# 13-AM64x-02.net
KiCad netlist of a schematic drawn in Altium Designer
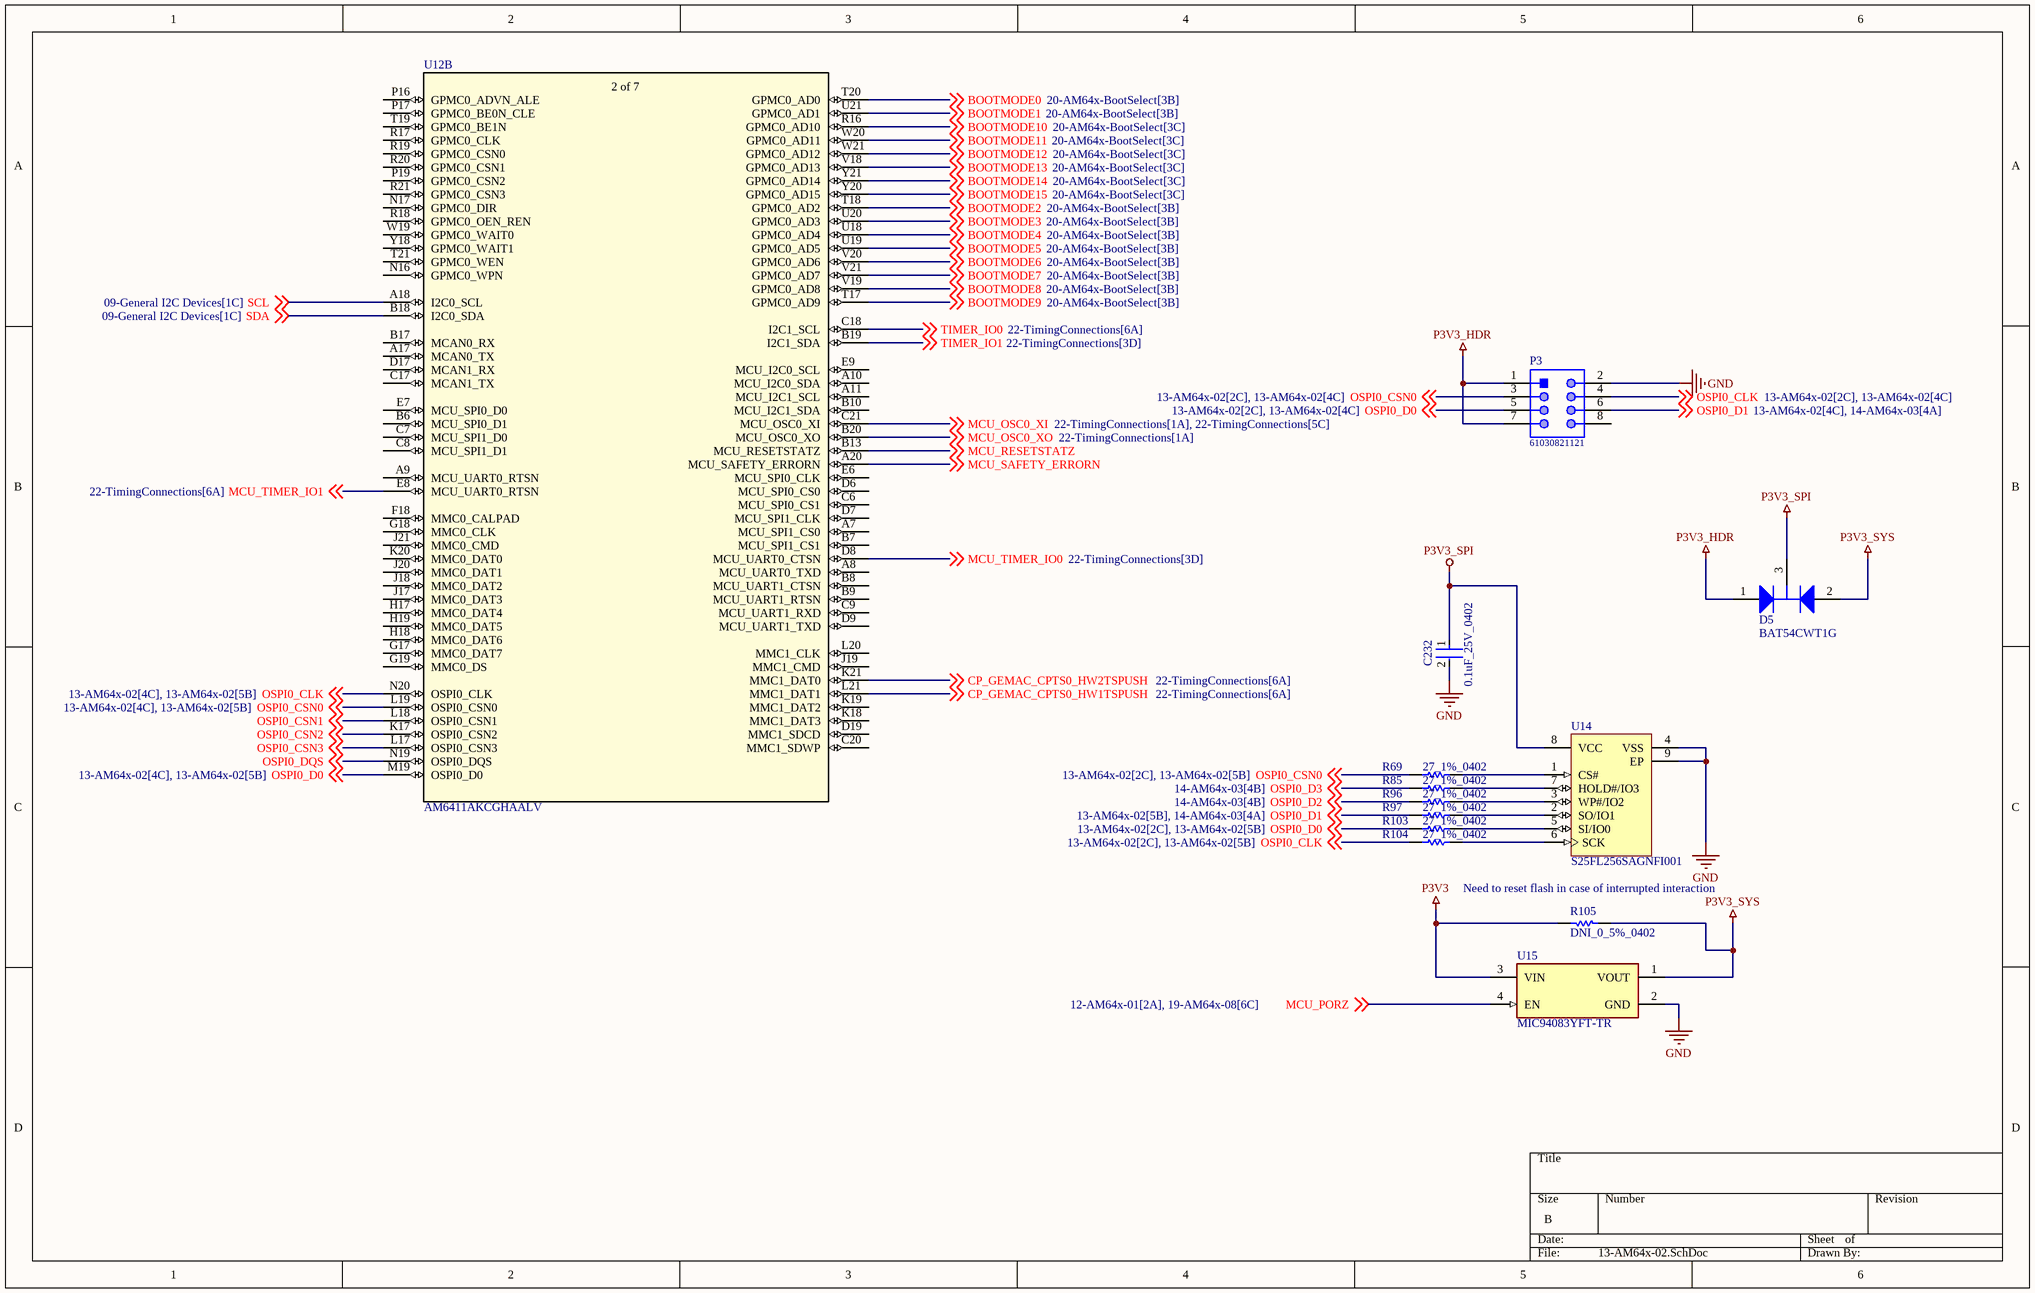
[diagram p0: 13-AM64x-02.SchDoc]

(export (version "E")
  (design (tool "Eeschema 10.0.6"))
  (components
    (comp (ref "C232")
      (value "0.1uF_25V_0402")
      (footprint "FP-0402-L_1_0_1-W_0_5_0_1-IPC_C")
      (description "General Purpose Ceramic Capacitor, 0402, 100nF, 10%, X7R, 15%, 25V")
      (fields (field (name "VOLTAGE") "25V") (field (name "TOLERANCE") "10%"))
      (libsource (lib "Altium Content Vault") (part "b4654b650e69147ec39a6b967a45e02"))
    )
    (comp (ref "D5")
      (value "BAT54CWT1G")
      (footprint "ONSC-SOT-323-3-419-04_V")
      (description "Dual Series Cathode Schottky Barrier Diodes, 3-Pin SOT-323, Pb-Free, Tape and Reel")
      (fields (field (name "MANUFACTURER") "On Semiconductor"))
      (libsource (lib "Altium Content Vault") (part "ONSC-D-A1A2K3-3"))
    )
    (comp (ref "P3")
      (value "61030821121")
      (footprint "61030821121")
      (description "SMT Vertical Pin Header WR-PHD, Pitch 2.54 mm, Dual Row, 8 pins")
      (fields (field (name "MANUFACTURER") "Wurth Elektronik") (field (name "PUBLISHER") "WurthElektronik"))
      (libsource (lib "Altium Content Vault") (part "WE-CN-2P-M-R8"))
    )
    (comp (ref "R69")
      (value "27_1%_0402")
      (footprint "RESC1005X40X25NL05T05")
      (fields (field (name "PART NUMBER") "CRCW040227R0FKED") (field (name "MANUFACTURER") "Vishay Dale"))
      (libsource (lib "Altium Content Vault") (part "RES"))
    )
    (comp (ref "R85")
      (value "27_1%_0402")
      (footprint "RESC1005X40X25NL05T05")
      (fields (field (name "PART NUMBER") "CRCW040227R0FKED") (field (name "MANUFACTURER") "Vishay Dale"))
      (libsource (lib "Altium Content Vault") (part "RES"))
    )
    (comp (ref "R96")
      (value "27_1%_0402")
      (footprint "RESC1005X40X25NL05T05")
      (fields (field (name "PART NUMBER") "CRCW040227R0FKED") (field (name "MANUFACTURER") "Vishay Dale"))
      (libsource (lib "Altium Content Vault") (part "RES"))
    )
    (comp (ref "R97")
      (value "27_1%_0402")
      (footprint "RESC1005X40X25NL05T05")
      (fields (field (name "PART NUMBER") "CRCW040227R0FKED") (field (name "MANUFACTURER") "Vishay Dale"))
      (libsource (lib "Altium Content Vault") (part "RES"))
    )
    (comp (ref "R103")
      (value "27_1%_0402")
      (footprint "RESC1005X40X25NL05T05")
      (fields (field (name "PART NUMBER") "CRCW040227R0FKED") (field (name "MANUFACTURER") "Vishay Dale"))
      (libsource (lib "Altium Content Vault") (part "RES"))
    )
    (comp (ref "R104")
      (value "27_1%_0402")
      (footprint "RESC1005X40X25NL05T05")
      (fields (field (name "PART NUMBER") "CRCW040227R0FKED") (field (name "MANUFACTURER") "Vishay Dale"))
      (libsource (lib "Altium Content Vault") (part "RES"))
    )
    (comp (ref "R105")
      (value "DNI_0_5%_0402")
      (footprint "RESC1005X40X25LL10T10")
      (fields (field (name "MANUFACTURER") "KOA Speer") (field (name "PART NUMBER") "RK73Z1ETTP"))
      (libsource (lib "Altium Content Vault") (part "RES"))
    )
    (comp (ref "U12")
      (value "AM6411AKCGHAALV")
      (footprint "FCBGA441_ALV_TEX")
      (description "No Description Available")
      (libsource (lib "AM6411AKCGHAALV") (part "AM6411AKCGHAALV"))
    )
    (comp (ref "U14")
      (value "S25FL256SAGNFI001")
      (footprint "CYP-WSON-8_L")
      (description "SPI Flash Memory, 2.7 to 3.6 V, -40 to 85 degC, 8-Pin WSON, RoHS, Tube")
      (fields (field (name "MANUFACTURER") "CypressSemiconductorCorp"))
      (libsource (lib "Altium Content Vault") (part "CYP-S25FL256S-WSON-8"))
    )
    (comp (ref "U15")
      (value "MIC94083YFT-TR")
      (footprint "FP-FTDFN085085-4LD-PL-1-MFG")
      (description "IC PWR SWITCH P-CHAN 1:1 4TMLF")
      (libsource (lib "Altium Content Vault") (part "f982b0e4379ad1be1c154354d61e319"))
    )
  )
  (nets
    (net (code "1") (name "BOOTMODE0") (class "Default")
      (node (ref "U12") (pin "T20") (pinfunction "GPMC0_AD0_T20") (pintype "bidirectional"))
    )
    (net (code "2") (name "BOOTMODE1") (class "Default")
      (node (ref "U12") (pin "U21") (pinfunction "GPMC0_AD1_U21") (pintype "bidirectional"))
    )
    (net (code "3") (name "BOOTMODE2") (class "Default")
      (node (ref "U12") (pin "T18") (pinfunction "GPMC0_AD2_T18") (pintype "bidirectional"))
    )
    (net (code "4") (name "BOOTMODE3") (class "Default")
      (node (ref "U12") (pin "U20") (pinfunction "GPMC0_AD3_U20") (pintype "bidirectional"))
    )
    (net (code "5") (name "BOOTMODE4") (class "Default")
      (node (ref "U12") (pin "U18") (pinfunction "GPMC0_AD4_U18") (pintype "bidirectional"))
    )
    (net (code "6") (name "BOOTMODE5") (class "Default")
      (node (ref "U12") (pin "U19") (pinfunction "GPMC0_AD5_U19") (pintype "bidirectional"))
    )
    (net (code "7") (name "BOOTMODE6") (class "Default")
      (node (ref "U12") (pin "V20") (pinfunction "GPMC0_AD6_V20") (pintype "bidirectional"))
    )
    (net (code "8") (name "BOOTMODE7") (class "Default")
      (node (ref "U12") (pin "V21") (pinfunction "GPMC0_AD7_V21") (pintype "bidirectional"))
    )
    (net (code "9") (name "BOOTMODE8") (class "Default")
      (node (ref "U12") (pin "V19") (pinfunction "GPMC0_AD8_V19") (pintype "bidirectional"))
    )
    (net (code "10") (name "BOOTMODE9") (class "Default")
      (node (ref "U12") (pin "T17") (pinfunction "GPMC0_AD9_T17") (pintype "bidirectional"))
    )
    (net (code "11") (name "BOOTMODE10") (class "Default")
      (node (ref "U12") (pin "R16") (pinfunction "GPMC0_AD10_R16") (pintype "bidirectional"))
    )
    (net (code "12") (name "BOOTMODE11") (class "Default")
      (node (ref "U12") (pin "W20") (pinfunction "GPMC0_AD11_W20") (pintype "bidirectional"))
    )
    (net (code "13") (name "BOOTMODE12") (class "Default")
      (node (ref "U12") (pin "W21") (pinfunction "GPMC0_AD12_W21") (pintype "bidirectional"))
    )
    (net (code "14") (name "BOOTMODE13") (class "Default")
      (node (ref "U12") (pin "V18") (pinfunction "GPMC0_AD13_V18") (pintype "bidirectional"))
    )
    (net (code "15") (name "BOOTMODE14") (class "Default")
      (node (ref "U12") (pin "Y21") (pinfunction "GPMC0_AD14_Y21") (pintype "bidirectional"))
    )
    (net (code "16") (name "BOOTMODE15") (class "Default")
      (node (ref "U12") (pin "Y20") (pinfunction "GPMC0_AD15_Y20") (pintype "bidirectional"))
    )
    (net (code "17") (name "CP_GEMAC_CPTS0_HW1TSPUSH") (class "Default")
      (node (ref "U12") (pin "L21") (pinfunction "MMC1_DAT1_L21") (pintype "bidirectional"))
    )
    (net (code "18") (name "CP_GEMAC_CPTS0_HW2TSPUSH") (class "Default")
      (node (ref "U12") (pin "K21") (pinfunction "MMC1_DAT0_K21") (pintype "bidirectional"))
    )
    (net (code "19") (name "GND") (class "Default")
      (node (ref "C232") (pin "2") (pinfunction "2_2") (pintype "passive"))
      (node (ref "P3") (pin "2") (pinfunction "2_2") (pintype "passive"))
      (node (ref "U14") (pin "4") (pinfunction "VSS_4") (pintype "power_in"))
      (node (ref "U14") (pin "9") (pinfunction "EP_9") (pintype "passive"))
      (node (ref "U15") (pin "2") (pinfunction "GND_2") (pintype "power_in"))
    )
    (net (code "20") (name "MCU_OSC0_XI") (class "Default")
      (node (ref "U12") (pin "C21") (pinfunction "MCU_OSC0_XI_C21") (pintype "bidirectional"))
    )
    (net (code "21") (name "MCU_OSC0_XO") (class "Default")
      (node (ref "U12") (pin "B20") (pinfunction "MCU_OSC0_XO_B20") (pintype "bidirectional"))
    )
    (net (code "22") (name "MCU_PORZ") (class "Default")
      (node (ref "U15") (pin "4") (pinfunction "EN_4") (pintype "input"))
    )
    (net (code "23") (name "MCU_RESETSTATZ") (class "Default")
      (node (ref "U12") (pin "B13") (pinfunction "MCU_RESETSTATZ_B13") (pintype "bidirectional"))
    )
    (net (code "24") (name "MCU_SAFETY_ERRORN") (class "Default")
      (node (ref "U12") (pin "A20") (pinfunction "MCU_SAFETY_ERRORN_A20") (pintype "bidirectional"))
    )
    (net (code "25") (name "MCU_TIMER_IO0") (class "Default")
      (node (ref "U12") (pin "D8") (pinfunction "MCU_UART0_CTSN_D8") (pintype "bidirectional"))
    )
    (net (code "26") (name "MCU_TIMER_IO1") (class "Default")
      (node (ref "U12") (pin "E8") (pinfunction "MCU_UART0_RTSN_E8") (pintype "bidirectional"))
    )
    (net (code "27") (name "Net-(U14-CS#)") (class "Default")
      (node (ref "R69") (pin "2") (pinfunction "2_2") (pintype "passive"))
      (node (ref "U14") (pin "1") (pinfunction "CS#_1") (pintype "input"))
    )
    (net (code "28") (name "Net-(U14-HOLD#{slash}IO3)") (class "Default")
      (node (ref "R85") (pin "2") (pinfunction "2_2") (pintype "passive"))
      (node (ref "U14") (pin "7") (pinfunction "HOLD#/IO3_7") (pintype "bidirectional"))
    )
    (net (code "29") (name "Net-(U14-SCK)") (class "Default")
      (node (ref "R104") (pin "2") (pinfunction "2_2") (pintype "passive"))
      (node (ref "U14") (pin "6") (pinfunction "SCK_6") (pintype "input"))
    )
    (net (code "30") (name "Net-(U14-SI{slash}IO0)") (class "Default")
      (node (ref "R103") (pin "2") (pinfunction "2_2") (pintype "passive"))
      (node (ref "U14") (pin "5") (pinfunction "SI/IO0_5") (pintype "bidirectional"))
    )
    (net (code "31") (name "Net-(U14-SO{slash}IO1)") (class "Default")
      (node (ref "R97") (pin "2") (pinfunction "2_2") (pintype "passive"))
      (node (ref "U14") (pin "2") (pinfunction "SO/IO1_2") (pintype "bidirectional"))
    )
    (net (code "32") (name "Net-(U14-WP#{slash}IO2)") (class "Default")
      (node (ref "R96") (pin "2") (pinfunction "2_2") (pintype "passive"))
      (node (ref "U14") (pin "3") (pinfunction "WP#/IO2_3") (pintype "bidirectional"))
    )
    (net (code "33") (name "OSPI0_CLK") (class "Default")
      (node (ref "P3") (pin "4") (pinfunction "4_4") (pintype "passive"))
      (node (ref "R104") (pin "1") (pinfunction "1_1") (pintype "passive"))
      (node (ref "U12") (pin "N20") (pinfunction "OSPI0_CLK_N20") (pintype "bidirectional"))
    )
    (net (code "34") (name "OSPI0_CSN0") (class "Default")
      (node (ref "P3") (pin "3") (pinfunction "3_3") (pintype "passive"))
      (node (ref "R69") (pin "1") (pinfunction "1_1") (pintype "passive"))
      (node (ref "U12") (pin "L19") (pinfunction "OSPI0_CSN0_L19") (pintype "bidirectional"))
    )
    (net (code "35") (name "OSPI0_CSN1") (class "Default")
      (node (ref "U12") (pin "L18") (pinfunction "OSPI0_CSN1_L18") (pintype "bidirectional"))
    )
    (net (code "36") (name "OSPI0_CSN2") (class "Default")
      (node (ref "U12") (pin "K17") (pinfunction "OSPI0_CSN2_K17") (pintype "bidirectional"))
    )
    (net (code "37") (name "OSPI0_CSN3") (class "Default")
      (node (ref "U12") (pin "L17") (pinfunction "OSPI0_CSN3_L17") (pintype "bidirectional"))
    )
    (net (code "38") (name "OSPI0_D0") (class "Default")
      (node (ref "P3") (pin "5") (pinfunction "5_5") (pintype "passive"))
      (node (ref "R103") (pin "1") (pinfunction "1_1") (pintype "passive"))
      (node (ref "U12") (pin "M19") (pinfunction "OSPI0_D0_M19") (pintype "bidirectional"))
    )
    (net (code "39") (name "OSPI0_D1") (class "Default")
      (node (ref "P3") (pin "6") (pinfunction "6_6") (pintype "passive"))
      (node (ref "R97") (pin "1") (pinfunction "1_1") (pintype "passive"))
    )
    (net (code "40") (name "OSPI0_D2") (class "Default")
      (node (ref "R96") (pin "1") (pinfunction "1_1") (pintype "passive"))
    )
    (net (code "41") (name "OSPI0_D3") (class "Default")
      (node (ref "R85") (pin "1") (pinfunction "1_1") (pintype "passive"))
    )
    (net (code "42") (name "OSPI0_DQS") (class "Default")
      (node (ref "U12") (pin "N19") (pinfunction "OSPI0_DQS_N19") (pintype "bidirectional"))
    )
    (net (code "43") (name "P3V3") (class "Default")
      (node (ref "R105") (pin "1") (pinfunction "1_1") (pintype "passive"))
      (node (ref "U15") (pin "3") (pinfunction "VIN_3") (pintype "power_in"))
    )
    (net (code "44") (name "P3V3_HDR") (class "Default")
      (node (ref "D5") (pin "1") (pinfunction "A1_1") (pintype "passive"))
      (node (ref "P3") (pin "1") (pinfunction "1_1") (pintype "passive"))
      (node (ref "P3") (pin "7") (pinfunction "7_7") (pintype "passive"))
    )
    (net (code "45") (name "P3V3_SPI") (class "Default")
      (node (ref "C232") (pin "1") (pinfunction "1_1") (pintype "passive"))
      (node (ref "D5") (pin "3") (pinfunction "K_3") (pintype "passive"))
      (node (ref "U14") (pin "8") (pinfunction "VCC_8") (pintype "power_in"))
    )
    (net (code "46") (name "P3V3_SYS") (class "Default")
      (node (ref "D5") (pin "2") (pinfunction "A2_2") (pintype "passive"))
      (node (ref "R105") (pin "2") (pinfunction "2_2") (pintype "passive"))
      (node (ref "U15") (pin "1") (pinfunction "VOUT_1") (pintype "power_in"))
    )
    (net (code "47") (name "SCL") (class "Default")
      (node (ref "U12") (pin "A18") (pinfunction "I2C0_SCL_A18") (pintype "bidirectional"))
    )
    (net (code "48") (name "SDA") (class "Default")
      (node (ref "U12") (pin "B18") (pinfunction "I2C0_SDA_B18") (pintype "bidirectional"))
    )
    (net (code "49") (name "TIMER_IO0") (class "Default")
      (node (ref "U12") (pin "C18") (pinfunction "I2C1_SCL_C18") (pintype "bidirectional"))
    )
    (net (code "50") (name "TIMER_IO1") (class "Default")
      (node (ref "U12") (pin "B19") (pinfunction "I2C1_SDA_B19") (pintype "bidirectional"))
    )
    (net (code "51") (name "unconnected-(P3-Pad8)") (class "Default")
      (node (ref "P3") (pin "8") (pinfunction "8_8") (pintype "passive"))
    )
    (net (code "52") (name "unconnected-(U12B-GPMC0_ADVN_ALE-PadP16)") (class "Default")
      (node (ref "U12") (pin "P16") (pinfunction "GPMC0_ADVN_ALE_P16") (pintype "bidirectional"))
    )
    (net (code "53") (name "unconnected-(U12B-GPMC0_BE0N_CLE-PadP17)") (class "Default")
      (node (ref "U12") (pin "P17") (pinfunction "GPMC0_BE0N_CLE_P17") (pintype "bidirectional"))
    )
    (net (code "54") (name "unconnected-(U12B-GPMC0_BE1N-PadT19)") (class "Default")
      (node (ref "U12") (pin "T19") (pinfunction "GPMC0_BE1N_T19") (pintype "bidirectional"))
    )
    (net (code "55") (name "unconnected-(U12B-GPMC0_CLK-PadR17)") (class "Default")
      (node (ref "U12") (pin "R17") (pinfunction "GPMC0_CLK_R17") (pintype "bidirectional"))
    )
    (net (code "56") (name "unconnected-(U12B-GPMC0_CSN0-PadR19)") (class "Default")
      (node (ref "U12") (pin "R19") (pinfunction "GPMC0_CSN0_R19") (pintype "bidirectional"))
    )
    (net (code "57") (name "unconnected-(U12B-GPMC0_CSN1-PadR20)") (class "Default")
      (node (ref "U12") (pin "R20") (pinfunction "GPMC0_CSN1_R20") (pintype "bidirectional"))
    )
    (net (code "58") (name "unconnected-(U12B-GPMC0_CSN2-PadP19)") (class "Default")
      (node (ref "U12") (pin "P19") (pinfunction "GPMC0_CSN2_P19") (pintype "bidirectional"))
    )
    (net (code "59") (name "unconnected-(U12B-GPMC0_CSN3-PadR21)") (class "Default")
      (node (ref "U12") (pin "R21") (pinfunction "GPMC0_CSN3_R21") (pintype "bidirectional"))
    )
    (net (code "60") (name "unconnected-(U12B-GPMC0_DIR-PadN17)") (class "Default")
      (node (ref "U12") (pin "N17") (pinfunction "GPMC0_DIR_N17") (pintype "bidirectional"))
    )
    (net (code "61") (name "unconnected-(U12B-GPMC0_OEN_REN-PadR18)") (class "Default")
      (node (ref "U12") (pin "R18") (pinfunction "GPMC0_OEN_REN_R18") (pintype "bidirectional"))
    )
    (net (code "62") (name "unconnected-(U12B-GPMC0_WAIT0-PadW19)") (class "Default")
      (node (ref "U12") (pin "W19") (pinfunction "GPMC0_WAIT0_W19") (pintype "bidirectional"))
    )
    (net (code "63") (name "unconnected-(U12B-GPMC0_WAIT1-PadY18)") (class "Default")
      (node (ref "U12") (pin "Y18") (pinfunction "GPMC0_WAIT1_Y18") (pintype "bidirectional"))
    )
    (net (code "64") (name "unconnected-(U12B-GPMC0_WEN-PadT21)") (class "Default")
      (node (ref "U12") (pin "T21") (pinfunction "GPMC0_WEN_T21") (pintype "bidirectional"))
    )
    (net (code "65") (name "unconnected-(U12B-GPMC0_WPN-PadN16)") (class "Default")
      (node (ref "U12") (pin "N16") (pinfunction "GPMC0_WPN_N16") (pintype "bidirectional"))
    )
    (net (code "66") (name "unconnected-(U12B-MCAN0_RX-PadB17)") (class "Default")
      (node (ref "U12") (pin "B17") (pinfunction "MCAN0_RX_B17") (pintype "bidirectional"))
    )
    (net (code "67") (name "unconnected-(U12B-MCAN0_TX-PadA17)") (class "Default")
      (node (ref "U12") (pin "A17") (pinfunction "MCAN0_TX_A17") (pintype "bidirectional"))
    )
    (net (code "68") (name "unconnected-(U12B-MCAN1_RX-PadD17)") (class "Default")
      (node (ref "U12") (pin "D17") (pinfunction "MCAN1_RX_D17") (pintype "bidirectional"))
    )
    (net (code "69") (name "unconnected-(U12B-MCAN1_TX-PadC17)") (class "Default")
      (node (ref "U12") (pin "C17") (pinfunction "MCAN1_TX_C17") (pintype "bidirectional"))
    )
    (net (code "70") (name "unconnected-(U12B-MCU_I2C0_SCL-PadE9)") (class "Default")
      (node (ref "U12") (pin "E9") (pinfunction "MCU_I2C0_SCL_E9") (pintype "bidirectional"))
    )
    (net (code "71") (name "unconnected-(U12B-MCU_I2C0_SDA-PadA10)") (class "Default")
      (node (ref "U12") (pin "A10") (pinfunction "MCU_I2C0_SDA_A10") (pintype "bidirectional"))
    )
    (net (code "72") (name "unconnected-(U12B-MCU_I2C1_SCL-PadA11)") (class "Default")
      (node (ref "U12") (pin "A11") (pinfunction "MCU_I2C1_SCL_A11") (pintype "bidirectional"))
    )
    (net (code "73") (name "unconnected-(U12B-MCU_I2C1_SDA-PadB10)") (class "Default")
      (node (ref "U12") (pin "B10") (pinfunction "MCU_I2C1_SDA_B10") (pintype "bidirectional"))
    )
    (net (code "74") (name "unconnected-(U12B-MCU_SPI0_CLK-PadE6)") (class "Default")
      (node (ref "U12") (pin "E6") (pinfunction "MCU_SPI0_CLK_E6") (pintype "bidirectional"))
    )
    (net (code "75") (name "unconnected-(U12B-MCU_SPI0_CS0-PadD6)") (class "Default")
      (node (ref "U12") (pin "D6") (pinfunction "MCU_SPI0_CS0_D6") (pintype "bidirectional"))
    )
    (net (code "76") (name "unconnected-(U12B-MCU_SPI0_CS1-PadC6)") (class "Default")
      (node (ref "U12") (pin "C6") (pinfunction "MCU_SPI0_CS1_C6") (pintype "bidirectional"))
    )
    (net (code "77") (name "unconnected-(U12B-MCU_SPI0_D0-PadE7)") (class "Default")
      (node (ref "U12") (pin "E7") (pinfunction "MCU_SPI0_D0_E7") (pintype "bidirectional"))
    )
    (net (code "78") (name "unconnected-(U12B-MCU_SPI0_D1-PadB6)") (class "Default")
      (node (ref "U12") (pin "B6") (pinfunction "MCU_SPI0_D1_B6") (pintype "bidirectional"))
    )
    (net (code "79") (name "unconnected-(U12B-MCU_SPI1_CLK-PadD7)") (class "Default")
      (node (ref "U12") (pin "D7") (pinfunction "MCU_SPI1_CLK_D7") (pintype "bidirectional"))
    )
    (net (code "80") (name "unconnected-(U12B-MCU_SPI1_CS0-PadA7)") (class "Default")
      (node (ref "U12") (pin "A7") (pinfunction "MCU_SPI1_CS0_A7") (pintype "bidirectional"))
    )
    (net (code "81") (name "unconnected-(U12B-MCU_SPI1_CS1-PadB7)") (class "Default")
      (node (ref "U12") (pin "B7") (pinfunction "MCU_SPI1_CS1_B7") (pintype "bidirectional"))
    )
    (net (code "82") (name "unconnected-(U12B-MCU_SPI1_D0-PadC7)") (class "Default")
      (node (ref "U12") (pin "C7") (pinfunction "MCU_SPI1_D0_C7") (pintype "bidirectional"))
    )
    (net (code "83") (name "unconnected-(U12B-MCU_SPI1_D1-PadC8)") (class "Default")
      (node (ref "U12") (pin "C8") (pinfunction "MCU_SPI1_D1_C8") (pintype "bidirectional"))
    )
    (net (code "84") (name "unconnected-(U12B-MCU_UART0_RTSN-PadA9)") (class "Default")
      (node (ref "U12") (pin "A9") (pinfunction "MCU_UART0_RTSN_A9") (pintype "bidirectional"))
    )
    (net (code "85") (name "unconnected-(U12B-MCU_UART0_TXD-PadA8)") (class "Default")
      (node (ref "U12") (pin "A8") (pinfunction "MCU_UART0_TXD_A8") (pintype "bidirectional"))
    )
    (net (code "86") (name "unconnected-(U12B-MCU_UART1_CTSN-PadB8)") (class "Default")
      (node (ref "U12") (pin "B8") (pinfunction "MCU_UART1_CTSN_B8") (pintype "bidirectional"))
    )
    (net (code "87") (name "unconnected-(U12B-MCU_UART1_RTSN-PadB9)") (class "Default")
      (node (ref "U12") (pin "B9") (pinfunction "MCU_UART1_RTSN_B9") (pintype "bidirectional"))
    )
    (net (code "88") (name "unconnected-(U12B-MCU_UART1_RXD-PadC9)") (class "Default")
      (node (ref "U12") (pin "C9") (pinfunction "MCU_UART1_RXD_C9") (pintype "bidirectional"))
    )
    (net (code "89") (name "unconnected-(U12B-MCU_UART1_TXD-PadD9)") (class "Default")
      (node (ref "U12") (pin "D9") (pinfunction "MCU_UART1_TXD_D9") (pintype "bidirectional"))
    )
    (net (code "90") (name "unconnected-(U12B-MMC0_CALPAD-PadF18)") (class "Default")
      (node (ref "U12") (pin "F18") (pinfunction "MMC0_CALPAD_F18") (pintype "bidirectional"))
    )
    (net (code "91") (name "unconnected-(U12B-MMC0_CLK-PadG18)") (class "Default")
      (node (ref "U12") (pin "G18") (pinfunction "MMC0_CLK_G18") (pintype "bidirectional"))
    )
    (net (code "92") (name "unconnected-(U12B-MMC0_CMD-PadJ21)") (class "Default")
      (node (ref "U12") (pin "J21") (pinfunction "MMC0_CMD_J21") (pintype "bidirectional"))
    )
    (net (code "93") (name "unconnected-(U12B-MMC0_DAT0-PadK20)") (class "Default")
      (node (ref "U12") (pin "K20") (pinfunction "MMC0_DAT0_K20") (pintype "bidirectional"))
    )
    (net (code "94") (name "unconnected-(U12B-MMC0_DAT1-PadJ20)") (class "Default")
      (node (ref "U12") (pin "J20") (pinfunction "MMC0_DAT1_J20") (pintype "bidirectional"))
    )
    (net (code "95") (name "unconnected-(U12B-MMC0_DAT2-PadJ18)") (class "Default")
      (node (ref "U12") (pin "J18") (pinfunction "MMC0_DAT2_J18") (pintype "bidirectional"))
    )
    (net (code "96") (name "unconnected-(U12B-MMC0_DAT3-PadJ17)") (class "Default")
      (node (ref "U12") (pin "J17") (pinfunction "MMC0_DAT3_J17") (pintype "bidirectional"))
    )
    (net (code "97") (name "unconnected-(U12B-MMC0_DAT4-PadH17)") (class "Default")
      (node (ref "U12") (pin "H17") (pinfunction "MMC0_DAT4_H17") (pintype "bidirectional"))
    )
    (net (code "98") (name "unconnected-(U12B-MMC0_DAT5-PadH19)") (class "Default")
      (node (ref "U12") (pin "H19") (pinfunction "MMC0_DAT5_H19") (pintype "bidirectional"))
    )
    (net (code "99") (name "unconnected-(U12B-MMC0_DAT6-PadH18)") (class "Default")
      (node (ref "U12") (pin "H18") (pinfunction "MMC0_DAT6_H18") (pintype "bidirectional"))
    )
    (net (code "100") (name "unconnected-(U12B-MMC0_DAT7-PadG17)") (class "Default")
      (node (ref "U12") (pin "G17") (pinfunction "MMC0_DAT7_G17") (pintype "bidirectional"))
    )
    (net (code "101") (name "unconnected-(U12B-MMC0_DS-PadG19)") (class "Default")
      (node (ref "U12") (pin "G19") (pinfunction "MMC0_DS_G19") (pintype "bidirectional"))
    )
    (net (code "102") (name "unconnected-(U12B-MMC1_CLK-PadL20)") (class "Default")
      (node (ref "U12") (pin "L20") (pinfunction "MMC1_CLK_L20") (pintype "bidirectional"))
    )
    (net (code "103") (name "unconnected-(U12B-MMC1_CMD-PadJ19)") (class "Default")
      (node (ref "U12") (pin "J19") (pinfunction "MMC1_CMD_J19") (pintype "bidirectional"))
    )
    (net (code "104") (name "unconnected-(U12B-MMC1_DAT2-PadK19)") (class "Default")
      (node (ref "U12") (pin "K19") (pinfunction "MMC1_DAT2_K19") (pintype "bidirectional"))
    )
    (net (code "105") (name "unconnected-(U12B-MMC1_DAT3-PadK18)") (class "Default")
      (node (ref "U12") (pin "K18") (pinfunction "MMC1_DAT3_K18") (pintype "bidirectional"))
    )
    (net (code "106") (name "unconnected-(U12B-MMC1_SDCD-PadD19)") (class "Default")
      (node (ref "U12") (pin "D19") (pinfunction "MMC1_SDCD_D19") (pintype "bidirectional"))
    )
    (net (code "107") (name "unconnected-(U12B-MMC1_SDWP-PadC20)") (class "Default")
      (node (ref "U12") (pin "C20") (pinfunction "MMC1_SDWP_C20") (pintype "bidirectional"))
    )
  )
)
